# SevSeg-Shield-v11.net
KiCad netlist of a schematic drawn in EAGLE
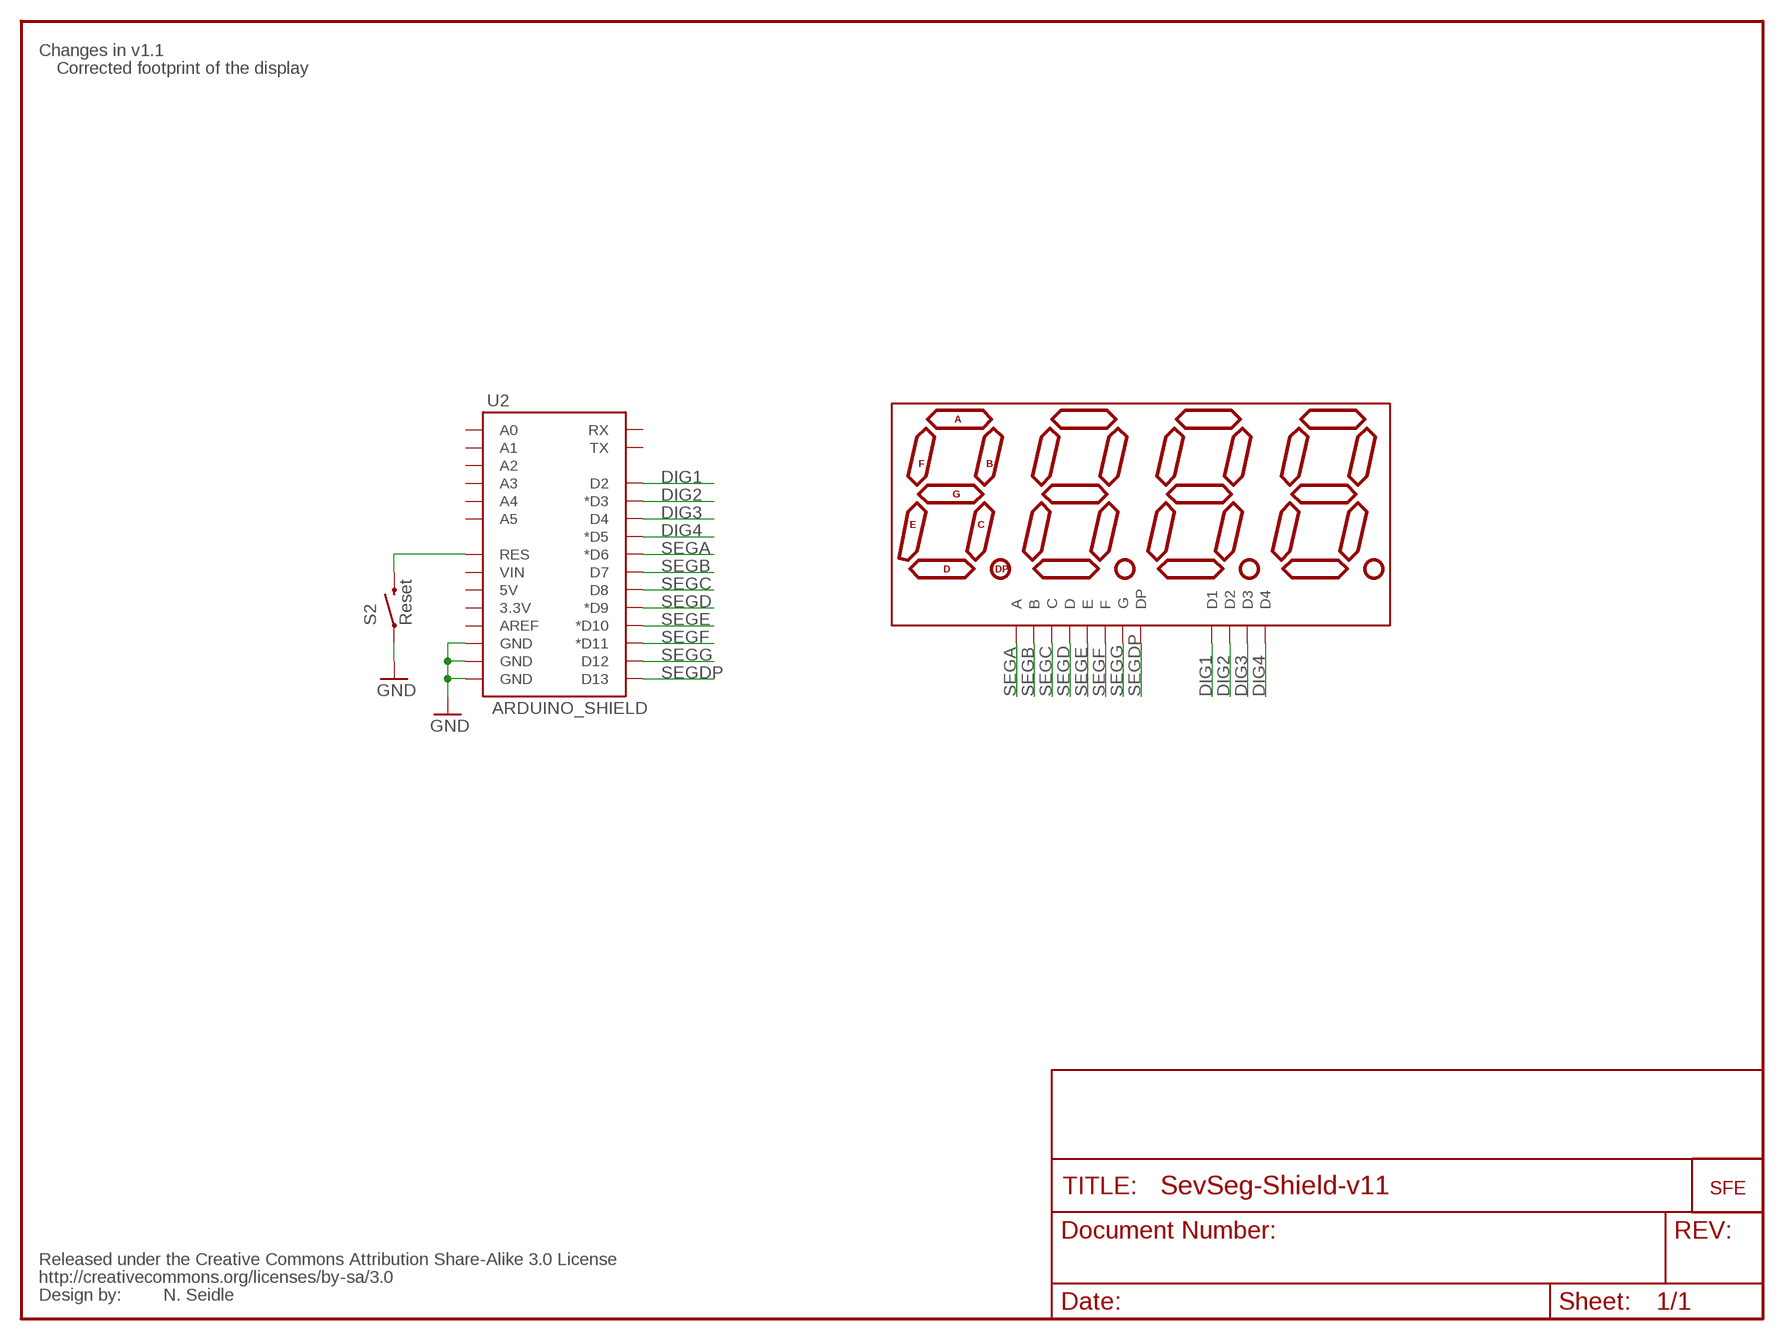
[diagram p0: schematic, sheet 1]

(export (version "E")
  (design (tool "Eeschema 10.0.6"))
  (components
    (comp (ref "S2")
      (value "Reset")
      (footprint "eagle-import:TACTILE-PTH")
      (libsource (lib "eagle-import") (part "SWITCH-MOMENTARY-2PTH"))
    )
    (comp (ref "U$1")
      (value "7-SEGMENT-4DIGIT-COUNTERPTH")
      (footprint "eagle-import:7-SEGMENT-4DIGIT-COUNTER")
      (libsource (lib "eagle-import") (part "7-SEGMENT-4DIGIT-COUNTERPTH"))
    )
    (comp (ref "U$3")
      (value "CREATIVE_COMMONS")
      (footprint "eagle-import:CREATIVE_COMMONS")
      (libsource (lib "eagle-import") (part "CREATIVE_COMMONS"))
    )
    (comp (ref "U$7")
      (value "LOGO-SFENEW")
      (footprint "eagle-import:SFE-NEW-WEBLOGO")
      (libsource (lib "eagle-import") (part "LOGO-SFENEW"))
    )
    (comp (ref "U2")
      (value "ARDUINO_SHIELD")
      (footprint "eagle-import:DUEMILANOVE_SHIELD")
      (libsource (lib "eagle-import") (part "ARDUINO_SHIELDLABEL"))
    )
  )
  (nets
    (net (code "1") (name "/DIG1") (class "Default")
      (node (ref "U$1") (pin "12") (pinfunction "D1_12") (pintype "bidirectional"))
      (node (ref "U2") (pin "D2") (pinfunction "D2_D2") (pintype "bidirectional"))
    )
    (net (code "2") (name "/DIG2") (class "Default")
      (node (ref "U$1") (pin "9") (pinfunction "D2_9") (pintype "bidirectional"))
      (node (ref "U2") (pin "D3") (pinfunction "*D3_D3") (pintype "bidirectional"))
    )
    (net (code "3") (name "/DIG3") (class "Default")
      (node (ref "U$1") (pin "8") (pinfunction "D3_8") (pintype "bidirectional"))
      (node (ref "U2") (pin "D4") (pinfunction "D4_D4") (pintype "bidirectional"))
    )
    (net (code "4") (name "/DIG4") (class "Default")
      (node (ref "U$1") (pin "6") (pinfunction "D4_6") (pintype "bidirectional"))
      (node (ref "U2") (pin "D5") (pinfunction "*D5_D5") (pintype "bidirectional"))
    )
    (net (code "5") (name "/SEGA") (class "Default")
      (node (ref "U$1") (pin "11") (pinfunction "A_11") (pintype "bidirectional"))
      (node (ref "U2") (pin "D6") (pinfunction "*D6_D6") (pintype "bidirectional"))
    )
    (net (code "6") (name "/SEGB") (class "Default")
      (node (ref "U$1") (pin "7") (pinfunction "B_7") (pintype "bidirectional"))
      (node (ref "U2") (pin "D7") (pinfunction "D7_D7") (pintype "bidirectional"))
    )
    (net (code "7") (name "/SEGC") (class "Default")
      (node (ref "U$1") (pin "4") (pinfunction "C_4") (pintype "bidirectional"))
      (node (ref "U2") (pin "D8") (pinfunction "D8_D8") (pintype "bidirectional"))
    )
    (net (code "8") (name "/SEGD") (class "Default")
      (node (ref "U$1") (pin "2") (pinfunction "D_2") (pintype "bidirectional"))
      (node (ref "U2") (pin "D9") (pinfunction "*D9_D9") (pintype "bidirectional"))
    )
    (net (code "9") (name "/SEGDP") (class "Default")
      (node (ref "U$1") (pin "3") (pinfunction "DP_3") (pintype "bidirectional"))
      (node (ref "U2") (pin "D13") (pinfunction "D13_D13") (pintype "bidirectional"))
    )
    (net (code "10") (name "/SEGE") (class "Default")
      (node (ref "U$1") (pin "1") (pinfunction "E_1") (pintype "bidirectional"))
      (node (ref "U2") (pin "D10") (pinfunction "*D10_D10") (pintype "bidirectional"))
    )
    (net (code "11") (name "/SEGF") (class "Default")
      (node (ref "U$1") (pin "10") (pinfunction "F_10") (pintype "bidirectional"))
      (node (ref "U2") (pin "D11") (pinfunction "*D11_D11") (pintype "bidirectional"))
    )
    (net (code "12") (name "/SEGG") (class "Default")
      (node (ref "U$1") (pin "5") (pinfunction "G_5") (pintype "bidirectional"))
      (node (ref "U2") (pin "D12") (pinfunction "D12_D12") (pintype "bidirectional"))
    )
    (net (code "13") (name "GND") (class "Default")
      (node (ref "S2") (pin "1") (pinfunction "1_1") (pintype "passive"))
      (node (ref "U2") (pin "GND@0") (pinfunction "GND_GND@0") (pintype "bidirectional"))
      (node (ref "U2") (pin "GND@1") (pinfunction "GND_GND@1") (pintype "bidirectional"))
      (node (ref "U2") (pin "GND@2") (pinfunction "GND_GND@2") (pintype "bidirectional"))
    )
    (net (code "14") (name "Net-(S2-2)") (class "Default")
      (node (ref "S2") (pin "3") (pinfunction "2_3") (pintype "passive"))
      (node (ref "U2") (pin "RES") (pinfunction "RES_RES") (pintype "bidirectional"))
    )
    (net (code "15") (name "unconnected-(U2-Pad3.3V)") (class "Default")
      (node (ref "U2") (pin "3.3V") (pinfunction "3.3V_3.3V") (pintype "bidirectional"))
    )
    (net (code "16") (name "unconnected-(U2-Pad5V)") (class "Default")
      (node (ref "U2") (pin "5V") (pinfunction "5V_5V") (pintype "bidirectional"))
    )
    (net (code "17") (name "unconnected-(U2-PadA0)") (class "Default")
      (node (ref "U2") (pin "A0") (pinfunction "A0_A0") (pintype "bidirectional"))
    )
    (net (code "18") (name "unconnected-(U2-PadA1)") (class "Default")
      (node (ref "U2") (pin "A1") (pinfunction "A1_A1") (pintype "bidirectional"))
    )
    (net (code "19") (name "unconnected-(U2-PadA2)") (class "Default")
      (node (ref "U2") (pin "A2") (pinfunction "A2_A2") (pintype "bidirectional"))
    )
    (net (code "20") (name "unconnected-(U2-PadA3)") (class "Default")
      (node (ref "U2") (pin "A3") (pinfunction "A3_A3") (pintype "bidirectional"))
    )
    (net (code "21") (name "unconnected-(U2-PadA4)") (class "Default")
      (node (ref "U2") (pin "A4") (pinfunction "A4_A4") (pintype "bidirectional"))
    )
    (net (code "22") (name "unconnected-(U2-PadA5)") (class "Default")
      (node (ref "U2") (pin "A5") (pinfunction "A5_A5") (pintype "bidirectional"))
    )
    (net (code "23") (name "unconnected-(U2-PadAREF)") (class "Default")
      (node (ref "U2") (pin "AREF") (pinfunction "AREF_AREF") (pintype "bidirectional"))
    )
    (net (code "24") (name "unconnected-(U2-PadRX)") (class "Default")
      (node (ref "U2") (pin "RX") (pinfunction "RX_RX") (pintype "bidirectional"))
    )
    (net (code "25") (name "unconnected-(U2-PadTX)") (class "Default")
      (node (ref "U2") (pin "TX") (pinfunction "TX_TX") (pintype "bidirectional"))
    )
    (net (code "26") (name "unconnected-(U2-PadVIN)") (class "Default")
      (node (ref "U2") (pin "VIN") (pinfunction "VIN_VIN") (pintype "bidirectional"))
    )
  )
)
